# PCB_INTER.net
KiCad netlist of a schematic drawn in Altium Designer
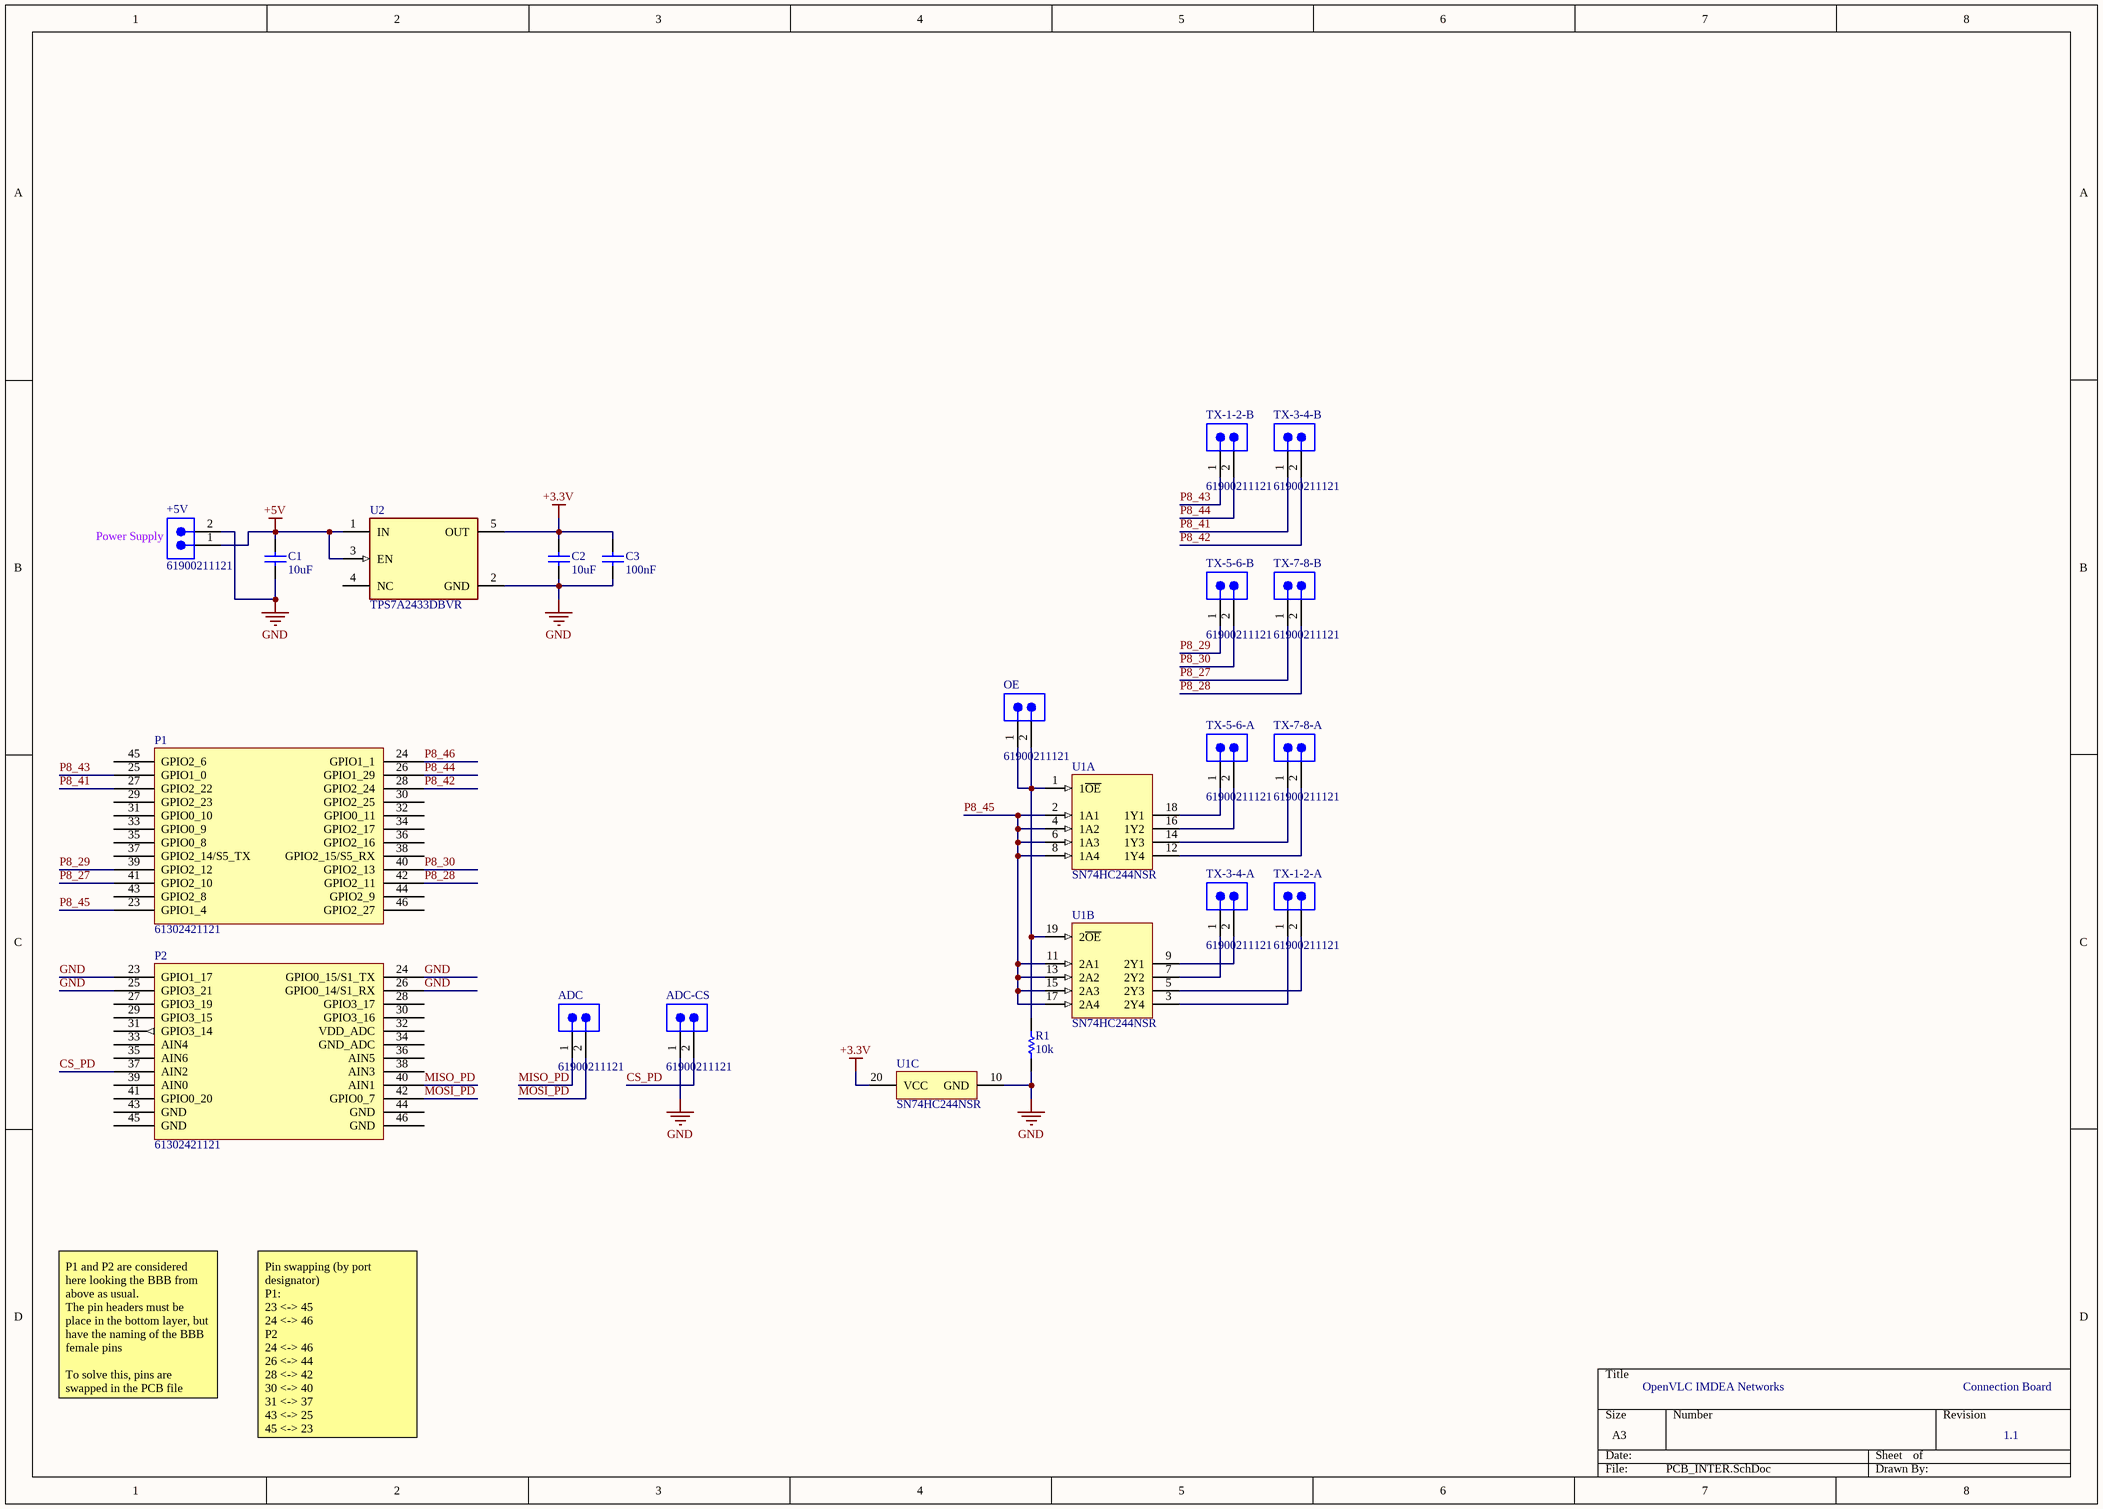
[diagram p0: PCB_INTER.SchDoc]

(export (version "E")
  (design (tool "Eeschema 10.0.6"))
  (components
    (comp (ref "+5V")
      (value "61900211121")
      (footprint "61900211121")
      (libsource (lib "Altium Content Vault") (part "Header_Male_1R_02P"))
    )
    (comp (ref "ADC")
      (value "61900211121")
      (footprint "61900211121")
      (libsource (lib "Altium Content Vault") (part "Header_Male_1R_02P"))
    )
    (comp (ref "ADC-CS")
      (value "61900211121")
      (footprint "61900211121")
      (libsource (lib "Altium Content Vault") (part "Header_Male_1R_02P"))
    )
    (comp (ref "C1")
      (value "10uF")
      (footprint "RESC1608X55N")
      (description "Capacitor")
      (fields (field (name "Comment") "GRM188R6YA106MA73D") (field (name "PUBLISHER") "Altium Limited"))
      (libsource (lib "Miscellaneous Devices") (part "Cap"))
    )
    (comp (ref "C2")
      (value "10uF")
      (footprint "RESC1608X55N")
      (description "Capacitor")
      (fields (field (name "Comment") "GRM188R6YA106MA73D") (field (name "PUBLISHER") "Altium Limited"))
      (libsource (lib "Miscellaneous Devices") (part "Cap"))
    )
    (comp (ref "C3")
      (value "100nF")
      (footprint "RESC1608X55N")
      (description "Capacitor")
      (fields (field (name "Comment") "GCM188R71H104KA57J") (field (name "PUBLISHER") "Altium Limited"))
      (libsource (lib "Miscellaneous Devices") (part "Cap"))
    )
    (comp (ref "OE")
      (value "61900211121")
      (footprint "61900211121")
      (libsource (lib "Altium Content Vault") (part "Header_Male_1R_02P"))
    )
    (comp (ref "P1")
      (value "61302421121")
      (footprint "BBB_CAPE_NO_HEADER_R_24")
      (libsource (lib "BeagleBoneCape") (part "BBB_P8_reduced"))
    )
    (comp (ref "P2")
      (value "61302421121")
      (footprint "BBB_CAPE_NO_HEADER_R_24")
      (libsource (lib "BeagleBoneCape") (part "BBB_P9_reduced"))
    )
    (comp (ref "R1")
      (value "10k")
      (footprint "RESC1608X55N")
      (description "Resistor")
      (fields (field (name "Comment") "RT0603BRD0710KL") (field (name "PUBLISHER") "Altium Limited"))
      (libsource (lib "Miscellaneous Devices") (part "Res1"))
    )
    (comp (ref "TX-1-2-A")
      (value "61900211121")
      (footprint "61900211121")
      (libsource (lib "Altium Content Vault") (part "Header_Male_1R_02P"))
    )
    (comp (ref "TX-1-2-B")
      (value "61900211121")
      (footprint "61900211121")
      (libsource (lib "Altium Content Vault") (part "Header_Male_1R_02P"))
    )
    (comp (ref "TX-3-4-A")
      (value "61900211121")
      (footprint "61900211121")
      (libsource (lib "Altium Content Vault") (part "Header_Male_1R_02P"))
    )
    (comp (ref "TX-3-4-B")
      (value "61900211121")
      (footprint "61900211121")
      (libsource (lib "Altium Content Vault") (part "Header_Male_1R_02P"))
    )
    (comp (ref "TX-5-6-A")
      (value "61900211121")
      (footprint "61900211121")
      (libsource (lib "Altium Content Vault") (part "Header_Male_1R_02P"))
    )
    (comp (ref "TX-5-6-B")
      (value "61900211121")
      (footprint "61900211121")
      (libsource (lib "Altium Content Vault") (part "Header_Male_1R_02P"))
    )
    (comp (ref "TX-7-8-A")
      (value "61900211121")
      (footprint "61900211121")
      (libsource (lib "Altium Content Vault") (part "Header_Male_1R_02P"))
    )
    (comp (ref "TX-7-8-B")
      (value "61900211121")
      (footprint "61900211121")
      (libsource (lib "Altium Content Vault") (part "Header_Male_1R_02P"))
    )
    (comp (ref "U1")
      (value "SN74HC244NSR")
      (footprint "NS0020A_L")
      (description "Octal Buffers And Line Drivers With 3-State Outputs, NS0020A, LARGE T&R")
      (fields
        (field (name "GENERIC PART NUMBER") "SN74HC244")
        (field (name "MANUFACTURER") "Texas Instruments")
      )
      (libsource (lib "Altium Content Vault") (part "TI-SN54_74-XX020A-20"))
    )
    (comp (ref "U2")
      (value "TPS7A2433DBVR")
      (footprint "FP-DBV0005A-MFG")
      (libsource (lib "Altium Content Vault") (part "ee7747973c1ed1d4cccbb20406fa51c"))
    )
  )
  (nets
    (net (code "1") (name "+3.3V") (class "Default")
      (node (ref "C2") (pin "2") (pinfunction "2_2") (pintype "passive"))
      (node (ref "C3") (pin "1") (pinfunction "1_1") (pintype "passive"))
      (node (ref "U1") (pin "20") (pinfunction "VCC_20") (pintype "power_in"))
      (node (ref "U2") (pin "5") (pinfunction "OUT_5") (pintype "power_in"))
    )
    (net (code "2") (name "+5V") (class "Default")
      (node (ref "+5V") (pin "1") (pinfunction "1_1") (pintype "passive"))
      (node (ref "C1") (pin "1") (pinfunction "1_1") (pintype "passive"))
      (node (ref "U2") (pin "1") (pinfunction "IN_1") (pintype "power_in"))
      (node (ref "U2") (pin "3") (pinfunction "EN_3") (pintype "input"))
    )
    (net (code "3") (name "/CS_PD") (class "Default")
      (node (ref "ADC-CS") (pin "2") (pinfunction "2_2") (pintype "passive"))
      (node (ref "P2") (pin "37") (pinfunction "AIN2_37") (pintype "passive"))
    )
    (net (code "4") (name "/MISO_PD") (class "Default")
      (node (ref "ADC") (pin "1") (pinfunction "1_1") (pintype "passive"))
      (node (ref "P2") (pin "40") (pinfunction "AIN1_40") (pintype "passive"))
    )
    (net (code "5") (name "/MOSI_PD") (class "Default")
      (node (ref "ADC") (pin "2") (pinfunction "2_2") (pintype "passive"))
      (node (ref "P2") (pin "42") (pinfunction "GPIO0_7_42") (pintype "passive"))
    )
    (net (code "6") (name "/P8_27") (class "Default")
      (node (ref "P1") (pin "41") (pinfunction "GPIO2_10_41") (pintype "passive"))
      (node (ref "TX-7-8-B") (pin "1") (pinfunction "1_1") (pintype "passive"))
    )
    (net (code "7") (name "/P8_28") (class "Default")
      (node (ref "P1") (pin "42") (pinfunction "GPIO2_11_42") (pintype "passive"))
      (node (ref "TX-7-8-B") (pin "2") (pinfunction "2_2") (pintype "passive"))
    )
    (net (code "8") (name "/P8_29") (class "Default")
      (node (ref "P1") (pin "39") (pinfunction "GPIO2_12_39") (pintype "passive"))
      (node (ref "TX-5-6-B") (pin "1") (pinfunction "1_1") (pintype "passive"))
    )
    (net (code "9") (name "/P8_30") (class "Default")
      (node (ref "P1") (pin "40") (pinfunction "GPIO2_13_40") (pintype "passive"))
      (node (ref "TX-5-6-B") (pin "2") (pinfunction "2_2") (pintype "passive"))
    )
    (net (code "10") (name "/P8_41") (class "Default")
      (node (ref "P1") (pin "27") (pinfunction "GPIO2_22_27") (pintype "passive"))
      (node (ref "TX-3-4-B") (pin "1") (pinfunction "1_1") (pintype "passive"))
    )
    (net (code "11") (name "/P8_42") (class "Default")
      (node (ref "P1") (pin "28") (pinfunction "GPIO2_24_28") (pintype "passive"))
      (node (ref "TX-3-4-B") (pin "2") (pinfunction "2_2") (pintype "passive"))
    )
    (net (code "12") (name "/P8_43") (class "Default")
      (node (ref "P1") (pin "25") (pinfunction "GPIO1_0_25") (pintype "passive"))
      (node (ref "TX-1-2-B") (pin "1") (pinfunction "1_1") (pintype "passive"))
    )
    (net (code "13") (name "/P8_44") (class "Default")
      (node (ref "P1") (pin "26") (pinfunction "GPIO1_29_26") (pintype "passive"))
      (node (ref "TX-1-2-B") (pin "2") (pinfunction "2_2") (pintype "passive"))
    )
    (net (code "14") (name "/P8_45") (class "Default")
      (node (ref "P1") (pin "23") (pinfunction "GPIO1_4_23") (pintype "passive"))
      (node (ref "U1") (pin "11") (pinfunction "2A1_11") (pintype "input"))
      (node (ref "U1") (pin "13") (pinfunction "2A2_13") (pintype "input"))
      (node (ref "U1") (pin "15") (pinfunction "2A3_15") (pintype "input"))
      (node (ref "U1") (pin "17") (pinfunction "2A4_17") (pintype "input"))
      (node (ref "U1") (pin "2") (pinfunction "1A1_2") (pintype "input"))
      (node (ref "U1") (pin "4") (pinfunction "1A2_4") (pintype "input"))
      (node (ref "U1") (pin "6") (pinfunction "1A3_6") (pintype "input"))
      (node (ref "U1") (pin "8") (pinfunction "1A4_8") (pintype "input"))
    )
    (net (code "15") (name "/P8_46") (class "Default")
      (node (ref "P1") (pin "24") (pinfunction "GPIO1_1_24") (pintype "passive"))
    )
    (net (code "16") (name "GND") (class "Default")
      (node (ref "+5V") (pin "2") (pinfunction "2_2") (pintype "passive"))
      (node (ref "ADC-CS") (pin "1") (pinfunction "1_1") (pintype "passive"))
      (node (ref "C1") (pin "2") (pinfunction "2_2") (pintype "passive"))
      (node (ref "C2") (pin "1") (pinfunction "1_1") (pintype "passive"))
      (node (ref "C3") (pin "2") (pinfunction "2_2") (pintype "passive"))
      (node (ref "P2") (pin "23") (pinfunction "GPIO1_17_23") (pintype "passive"))
      (node (ref "P2") (pin "24") (pinfunction "GPIO0_15/S1_TX_24") (pintype "passive"))
      (node (ref "P2") (pin "25") (pinfunction "GPIO3_21_25") (pintype "passive"))
      (node (ref "P2") (pin "26") (pinfunction "GPIO0_14/S1_RX_26") (pintype "passive"))
      (node (ref "R1") (pin "2") (pinfunction "2_2") (pintype "passive"))
      (node (ref "U1") (pin "10") (pinfunction "GND_10") (pintype "power_in"))
      (node (ref "U2") (pin "2") (pinfunction "GND_2") (pintype "power_in"))
    )
    (net (code "17") (name "Net-(U1A-1Y1)") (class "Default")
      (node (ref "TX-5-6-A") (pin "1") (pinfunction "1_1") (pintype "passive"))
      (node (ref "U1") (pin "18") (pinfunction "1Y1_18") (pintype "tri_state"))
    )
    (net (code "18") (name "Net-(U1A-1Y2)") (class "Default")
      (node (ref "TX-5-6-A") (pin "2") (pinfunction "2_2") (pintype "passive"))
      (node (ref "U1") (pin "16") (pinfunction "1Y2_16") (pintype "tri_state"))
    )
    (net (code "19") (name "Net-(U1A-1Y3)") (class "Default")
      (node (ref "TX-7-8-A") (pin "1") (pinfunction "1_1") (pintype "passive"))
      (node (ref "U1") (pin "14") (pinfunction "1Y3_14") (pintype "tri_state"))
    )
    (net (code "20") (name "Net-(U1A-1Y4)") (class "Default")
      (node (ref "TX-7-8-A") (pin "2") (pinfunction "2_2") (pintype "passive"))
      (node (ref "U1") (pin "12") (pinfunction "1Y4_12") (pintype "tri_state"))
    )
    (net (code "21") (name "Net-(U1A-1~{OE})") (class "Default")
      (node (ref "OE") (pin "1") (pinfunction "1_1") (pintype "passive"))
      (node (ref "OE") (pin "2") (pinfunction "2_2") (pintype "passive"))
      (node (ref "R1") (pin "1") (pinfunction "1_1") (pintype "passive"))
      (node (ref "U1") (pin "1") (pinfunction "1~{OE}_1") (pintype "input"))
      (node (ref "U1") (pin "19") (pinfunction "2~{OE}_19") (pintype "input"))
    )
    (net (code "22") (name "Net-(U1B-2Y1)") (class "Default")
      (node (ref "TX-3-4-A") (pin "2") (pinfunction "2_2") (pintype "passive"))
      (node (ref "U1") (pin "9") (pinfunction "2Y1_9") (pintype "tri_state"))
    )
    (net (code "23") (name "Net-(U1B-2Y2)") (class "Default")
      (node (ref "TX-3-4-A") (pin "1") (pinfunction "1_1") (pintype "passive"))
      (node (ref "U1") (pin "7") (pinfunction "2Y2_7") (pintype "tri_state"))
    )
    (net (code "24") (name "Net-(U1B-2Y3)") (class "Default")
      (node (ref "TX-1-2-A") (pin "2") (pinfunction "2_2") (pintype "passive"))
      (node (ref "U1") (pin "5") (pinfunction "2Y3_5") (pintype "tri_state"))
    )
    (net (code "25") (name "Net-(U1B-2Y4)") (class "Default")
      (node (ref "TX-1-2-A") (pin "1") (pinfunction "1_1") (pintype "passive"))
      (node (ref "U1") (pin "3") (pinfunction "2Y4_3") (pintype "tri_state"))
    )
    (net (code "26") (name "unconnected-(P1-GPIO0_8-Pad35)") (class "Default")
      (node (ref "P1") (pin "35") (pinfunction "GPIO0_8_35") (pintype "passive"))
    )
    (net (code "27") (name "unconnected-(P1-GPIO0_9-Pad33)") (class "Default")
      (node (ref "P1") (pin "33") (pinfunction "GPIO0_9_33") (pintype "passive"))
    )
    (net (code "28") (name "unconnected-(P1-GPIO0_10-Pad31)") (class "Default")
      (node (ref "P1") (pin "31") (pinfunction "GPIO0_10_31") (pintype "passive"))
    )
    (net (code "29") (name "unconnected-(P1-GPIO0_11-Pad32)") (class "Default")
      (node (ref "P1") (pin "32") (pinfunction "GPIO0_11_32") (pintype "passive"))
    )
    (net (code "30") (name "unconnected-(P1-GPIO2_6-Pad45)") (class "Default")
      (node (ref "P1") (pin "45") (pinfunction "GPIO2_6_45") (pintype "passive"))
    )
    (net (code "31") (name "unconnected-(P1-GPIO2_8-Pad43)") (class "Default")
      (node (ref "P1") (pin "43") (pinfunction "GPIO2_8_43") (pintype "passive"))
    )
    (net (code "32") (name "unconnected-(P1-GPIO2_9-Pad44)") (class "Default")
      (node (ref "P1") (pin "44") (pinfunction "GPIO2_9_44") (pintype "passive"))
    )
    (net (code "33") (name "unconnected-(P1-GPIO2_14{slash}S5_TX-Pad37)") (class "Default")
      (node (ref "P1") (pin "37") (pinfunction "GPIO2_14/S5_TX_37") (pintype "passive"))
    )
    (net (code "34") (name "unconnected-(P1-GPIO2_15{slash}S5_RX-Pad38)") (class "Default")
      (node (ref "P1") (pin "38") (pinfunction "GPIO2_15/S5_RX_38") (pintype "passive"))
    )
    (net (code "35") (name "unconnected-(P1-GPIO2_16-Pad36)") (class "Default")
      (node (ref "P1") (pin "36") (pinfunction "GPIO2_16_36") (pintype "passive"))
    )
    (net (code "36") (name "unconnected-(P1-GPIO2_17-Pad34)") (class "Default")
      (node (ref "P1") (pin "34") (pinfunction "GPIO2_17_34") (pintype "passive"))
    )
    (net (code "37") (name "unconnected-(P1-GPIO2_23-Pad29)") (class "Default")
      (node (ref "P1") (pin "29") (pinfunction "GPIO2_23_29") (pintype "passive"))
    )
    (net (code "38") (name "unconnected-(P1-GPIO2_25-Pad30)") (class "Default")
      (node (ref "P1") (pin "30") (pinfunction "GPIO2_25_30") (pintype "passive"))
    )
    (net (code "39") (name "unconnected-(P1-GPIO2_27-Pad46)") (class "Default")
      (node (ref "P1") (pin "46") (pinfunction "GPIO2_27_46") (pintype "passive"))
    )
    (net (code "40") (name "unconnected-(P2-AIN0-Pad39)") (class "Default")
      (node (ref "P2") (pin "39") (pinfunction "AIN0_39") (pintype "passive"))
    )
    (net (code "41") (name "unconnected-(P2-AIN3-Pad38)") (class "Default")
      (node (ref "P2") (pin "38") (pinfunction "AIN3_38") (pintype "passive"))
    )
    (net (code "42") (name "unconnected-(P2-AIN4-Pad33)") (class "Default")
      (node (ref "P2") (pin "33") (pinfunction "AIN4_33") (pintype "passive"))
    )
    (net (code "43") (name "unconnected-(P2-AIN5-Pad36)") (class "Default")
      (node (ref "P2") (pin "36") (pinfunction "AIN5_36") (pintype "passive"))
    )
    (net (code "44") (name "unconnected-(P2-AIN6-Pad35)") (class "Default")
      (node (ref "P2") (pin "35") (pinfunction "AIN6_35") (pintype "passive"))
    )
    (net (code "45") (name "unconnected-(P2-GND-Pad43)") (class "Default")
      (node (ref "P2") (pin "43") (pinfunction "GND_43") (pintype "passive"))
    )
    (net (code "46") (name "unconnected-(P2-GND-Pad44)") (class "Default")
      (node (ref "P2") (pin "44") (pinfunction "GND_44") (pintype "passive"))
    )
    (net (code "47") (name "unconnected-(P2-GND-Pad45)") (class "Default")
      (node (ref "P2") (pin "45") (pinfunction "GND_45") (pintype "passive"))
    )
    (net (code "48") (name "unconnected-(P2-GND-Pad46)") (class "Default")
      (node (ref "P2") (pin "46") (pinfunction "GND_46") (pintype "passive"))
    )
    (net (code "49") (name "unconnected-(P2-GND_ADC-Pad34)") (class "Default")
      (node (ref "P2") (pin "34") (pinfunction "GND_ADC_34") (pintype "passive"))
    )
    (net (code "50") (name "unconnected-(P2-GPIO0_20-Pad41)") (class "Default")
      (node (ref "P2") (pin "41") (pinfunction "GPIO0_20_41") (pintype "passive"))
    )
    (net (code "51") (name "unconnected-(P2-GPIO3_14-Pad31)") (class "Default")
      (node (ref "P2") (pin "31") (pinfunction "GPIO3_14_31") (pintype "output"))
    )
    (net (code "52") (name "unconnected-(P2-GPIO3_15-Pad29)") (class "Default")
      (node (ref "P2") (pin "29") (pinfunction "GPIO3_15_29") (pintype "passive"))
    )
    (net (code "53") (name "unconnected-(P2-GPIO3_16-Pad30)") (class "Default")
      (node (ref "P2") (pin "30") (pinfunction "GPIO3_16_30") (pintype "passive"))
    )
    (net (code "54") (name "unconnected-(P2-GPIO3_17-Pad28)") (class "Default")
      (node (ref "P2") (pin "28") (pinfunction "GPIO3_17_28") (pintype "passive"))
    )
    (net (code "55") (name "unconnected-(P2-GPIO3_19-Pad27)") (class "Default")
      (node (ref "P2") (pin "27") (pinfunction "GPIO3_19_27") (pintype "passive"))
    )
    (net (code "56") (name "unconnected-(P2-VDD_ADC-Pad32)") (class "Default")
      (node (ref "P2") (pin "32") (pinfunction "VDD_ADC_32") (pintype "passive"))
    )
    (net (code "57") (name "unconnected-(U2-NC-Pad4)") (class "Default")
      (node (ref "U2") (pin "4") (pinfunction "NC_4") (pintype "passive"))
    )
  )
)
